# Power.net
KiCad netlist of a schematic drawn in Altium Designer
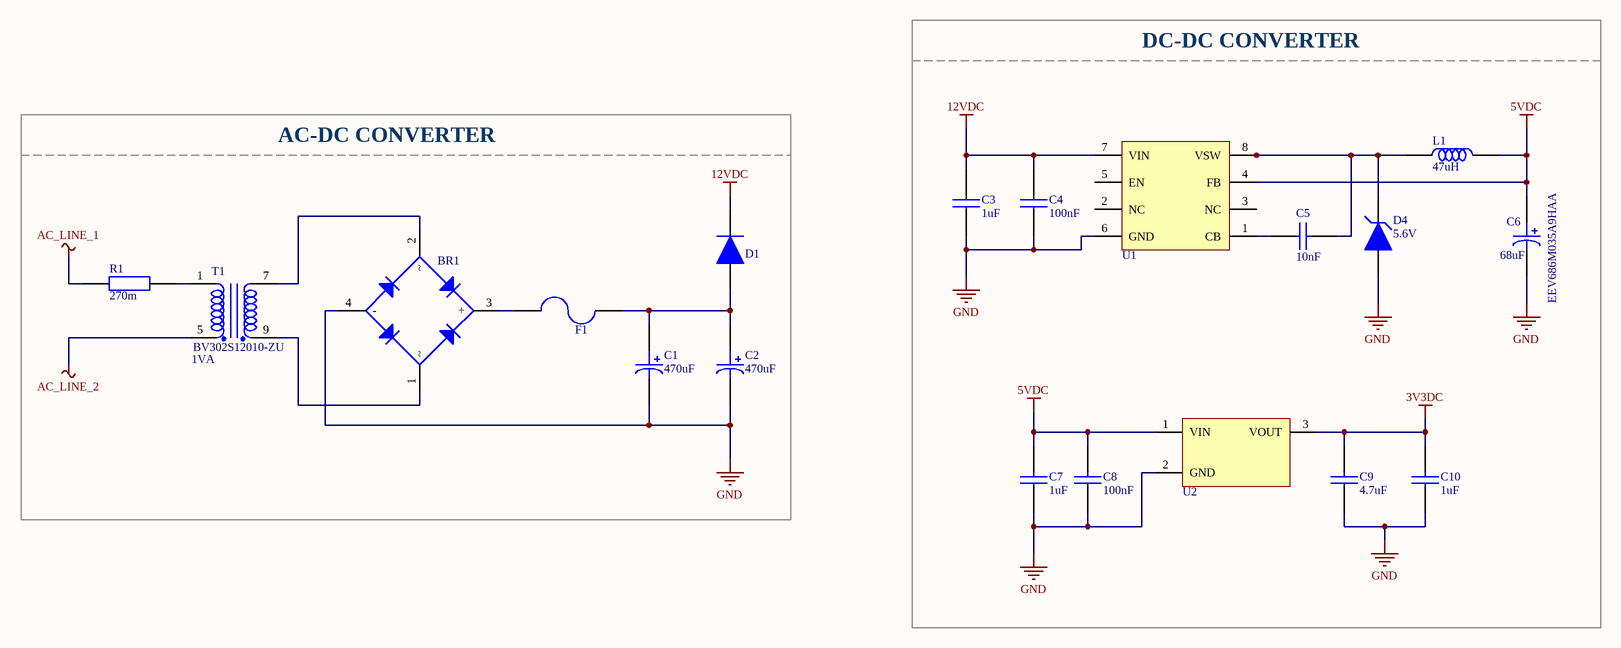
[diagram p0: Power.SchDoc]

(export (version "E")
  (design (tool "Eeschema 10.0.6"))
  (components
    (comp (ref "BR1")
      (value "DB105STR")
      (footprint "DB105STR")
      (description "Bridge Diode AC-DC")
      (fields (field (name "MANUFACTURER") "Sangdest Microelectronics") (field (name "DESIGNED BY") "BERK"))
      (libsource (lib "GuvenlikSistemi_Library") (part "DB105STR"))
    )
    (comp (ref "C1")
      (value "ESH477M050AH4AA")
      (footprint "CAP_RADIAL_D10_P5")
      (description "CAP ALU ELEC 470uF 50V RADIAL")
      (fields
        (field (name "MANUFACTURER") "KEMET")
        (field (name "TOLERANCE") "20%")
        (field (name "CAPACITANCE") "470uF")
        (field (name "DESIGNED BY") "BERK")
      )
      (libsource (lib "GuvenlikSistemi_Library") (part "CAP ALU ELEC 470uF 50V"))
    )
    (comp (ref "C2")
      (value "ESH477M050AH4AA")
      (footprint "CAP_RADIAL_D10_P5")
      (description "CAP ALU ELEC 470uF 50V RADIAL")
      (fields
        (field (name "MANUFACTURER") "KEMET")
        (field (name "TOLERANCE") "20%")
        (field (name "CAPACITANCE") "470uF")
        (field (name "DESIGNED BY") "BERK")
      )
      (libsource (lib "GuvenlikSistemi_Library") (part "CAP ALU ELEC 470uF 50V"))
    )
    (comp (ref "C3")
      (value "CL21B105KBFNNNE")
      (footprint "CAP_0805")
      (description "CAP CER 1uF %10 0805")
      (fields
        (field (name "MANUFACTURER") "Samsung")
        (field (name "TOLERANCE") "10%")
        (field (name "CAPACITANCE") "1uF")
        (field (name "DESIGNED BY") "BERK")
      )
      (libsource (lib "GuvenlikSistemi_Library") (part "CAP CER 1uF 0805"))
    )
    (comp (ref "C4")
      (value "CL21B104KBCNNNC")
      (footprint "CAP_0805")
      (description "CAP CER 100nF %10 0805")
      (fields
        (field (name "MANUFACTURER") "Samsung")
        (field (name "TOLERANCE") "10%")
        (field (name "CAPACITANCE") "100nF")
        (field (name "DESIGNED BY") "BERK")
      )
      (libsource (lib "GuvenlikSistemi_Library") (part "CAP CER 100nF 0805"))
    )
    (comp (ref "C5")
      (value "0603B103K160CT")
      (footprint "CAP_0603")
      (description "CAP CER 10nF %10 0603")
      (fields
        (field (name "MANUFACTURER") "Walsin Technologies")
        (field (name "TOLERANCE") "10%")
        (field (name "CAPACITANCE") "10nF")
        (field (name "DESIGNED BY") "BERK")
      )
      (libsource (lib "GuvenlikSistemi_Library") (part "CAP CER 10nF 0603"))
    )
    (comp (ref "C6")
      (value "EEV686M035A9HAA")
      (footprint "CAP_EEVseries")
      (description "Cap Aluminum Lytic 68uF 35V 20% (6.3 X 7.7mm) SMD 280mA 2000h 105C T/R")
      (fields
        (field (name "MANUFACTURER") "KEMET")
        (field (name "TOLERANCE") "20%")
        (field (name "CAPACITANCE") "68uF")
      )
      (libsource (lib "GuvenlikSistemi_Library") (part "CAP ALU 68uF"))
    )
    (comp (ref "C7")
      (value "CL21B105KBFNNNE")
      (footprint "CAP_0805")
      (description "CAP CER 1uF %10 0805")
      (fields
        (field (name "MANUFACTURER") "Samsung")
        (field (name "TOLERANCE") "10%")
        (field (name "CAPACITANCE") "1uF")
        (field (name "DESIGNED BY") "BERK")
      )
      (libsource (lib "GuvenlikSistemi_Library") (part "CAP CER 1uF 0805"))
    )
    (comp (ref "C8")
      (value "CL21B104KBCNNNC")
      (footprint "CAP_0805")
      (description "CAP CER 100nF %10 0805")
      (fields
        (field (name "MANUFACTURER") "Samsung")
        (field (name "TOLERANCE") "10%")
        (field (name "CAPACITANCE") "100nF")
        (field (name "DESIGNED BY") "BERK")
      )
      (libsource (lib "GuvenlikSistemi_Library") (part "CAP CER 100nF 0805"))
    )
    (comp (ref "C9")
      (value "CL21A475KAQNNNE")
      (footprint "CAP_0805")
      (description "CAP CER 4.7uF %10 0805")
      (fields
        (field (name "MANUFACTURER") "Samsung")
        (field (name "TOLERANCE") "10%")
        (field (name "CAPACITANCE") "4.7uF")
        (field (name "DESIGNED BY") "BERK")
      )
      (libsource (lib "GuvenlikSistemi_Library") (part "CAP CER 4.7uF 0805"))
    )
    (comp (ref "C10")
      (value "CL21B105KBFNNNE")
      (footprint "CAP_0805")
      (description "CAP CER 1uF %10 0805")
      (fields
        (field (name "MANUFACTURER") "Samsung")
        (field (name "TOLERANCE") "10%")
        (field (name "CAPACITANCE") "1uF")
        (field (name "DESIGNED BY") "BERK")
      )
      (libsource (lib "GuvenlikSistemi_Library") (part "CAP CER 1uF 0805"))
    )
    (comp (ref "D1")
      (value "1N4148WS")
      (footprint "SOD323F")
      (description "Diode, Single, 75 V, 150 mA, 1 V, 4 ns")
      (fields
        (field (name "MANUFACTURER") "ON Semiconductor / Fairchild")
        (field (name "DESIGNED BY") "BERK")
      )
      (libsource (lib "GuvenlikSistemi_Library") (part "1N4148WS"))
    )
    (comp (ref "D4")
      (value "1SMB5919BT3G")
      (footprint "SMB")
      (description "Diode Zener Single 5.6V 5% 3W 2-Pin SMB T/R")
      (fields
        (field (name "MANUFACTURER") "ON Semiconductor")
        (field (name "TOLERANCE") "5%")
        (field (name "WORKING VOLTAGE") "5.6V")
        (field (name "DESIGNED BY") "BERK")
      )
      (libsource (lib "GuvenlikSistemi_Library") (part "1SMB5919BT3G"))
    )
    (comp (ref "F1")
      (value "3413.0216.22")
      (footprint "3413.0216.22")
      (description "FUSE BRD MNT 1A 32VAC 63VDC 1206")
      (fields (field (name "MANUFACTURER") "Schurter") (field (name "DESIGNED BY") "BERK"))
      (libsource (lib "GuvenlikSistemi_Library") (part "FUSE 3413.0216.22"))
    )
    (comp (ref "L1")
      (value "78438335470")
      (footprint "IND_1212")
      (description "FIXED IND 47UH 390MA 2.3 OHM SMD")
      (fields
        (field (name "MANUFACTURER") "Wurth Electronics")
        (field (name "TOLERANCE") "30%")
        (field (name "INDUCTANCE") "47uH")
        (field (name "DESIGNED BY") "BERK")
      )
      (libsource (lib "GuvenlikSistemi_Library") (part "IND 47uH"))
    )
    (comp (ref "R1")
      (value "5WD27")
      (footprint "RES_AXIAL_W")
      (description "Resistor 5 Watt Cermet Wirewound Flameproof .27 Ohm 5% Axial Lead")
      (fields
        (field (name "MANUFACTURER") "NTE Electronics")
        (field (name "TOLERANCE") "5%")
        (field (name "RESISTANCE") "270m")
        (field (name "DESIGNED BY") "BERK")
      )
      (libsource (lib "GuvenlikSistemi_Library") (part "5WD27"))
    )
    (comp (ref "T1")
      (value "BV302S12010-ZU")
      (footprint "BV302S")
      (description "230-12 Transformer 1VA")
      (fields
        (field (name "MANUFACTURER") "Zettler Magnetics")
        (field (name "RATED POWER") "1VA")
        (field (name "DESIGNED BY") "BERK")
      )
      (libsource (lib "GuvenlikSistemi_Library") (part "BV302S12010-ZU"))
    )
    (comp (ref "U1")
      (value "LM2675MX-12/NOPB")
      (footprint "SOIC8")
      (description "Switching Voltage Regulators Pwr Cnvtr Hi Eff 1A SD Vtg Reg")
      (fields (field (name "MANUFACTURER") "TI National Semiconductor") (field (name "DESIGNED BY") "BERK"))
      (libsource (lib "GuvenlikSistemi_Library") (part "LM2675MX-12/NOPB"))
    )
    (comp (ref "U2")
      (value "AP7361-33E-13")
      (footprint "SOT223")
      (description "LDO Regulator Pos 3.3V 1A 4-Pin(3+Tab) SOT-223 T/R")
      (fields (field (name "MANUFACTURER") "Diodes") (field (name "DESIGNED BY") "BERK"))
      (libsource (lib "GuvenlikSistemi_Library") (part "AP7361-33E-13"))
    )
  )
  (nets
    (net (code "1") (name "3V3DC") (class "Default")
      (node (ref "C10") (pin "2") (pinfunction "2_2") (pintype "passive"))
      (node (ref "C9") (pin "2") (pinfunction "2_2") (pintype "passive"))
      (node (ref "U2") (pin "3") (pinfunction "VOUT_3") (pintype "passive"))
    )
    (net (code "2") (name "5VDC") (class "Default")
      (node (ref "C6") (pin "1") (pinfunction "1_1") (pintype "passive"))
      (node (ref "C7") (pin "2") (pinfunction "2_2") (pintype "passive"))
      (node (ref "C8") (pin "2") (pinfunction "2_2") (pintype "passive"))
      (node (ref "L1") (pin "2") (pinfunction "2_2") (pintype "passive"))
      (node (ref "U1") (pin "4") (pinfunction "FB_4") (pintype "passive"))
      (node (ref "U2") (pin "1") (pinfunction "VIN_1") (pintype "passive"))
    )
    (net (code "3") (name "12VDC") (class "Default")
      (node (ref "C3") (pin "2") (pinfunction "2_2") (pintype "passive"))
      (node (ref "C4") (pin "2") (pinfunction "2_2") (pintype "passive"))
      (node (ref "D1") (pin "1") (pinfunction "1_1") (pintype "power_in"))
      (node (ref "U1") (pin "7") (pinfunction "VIN_7") (pintype "passive"))
    )
    (net (code "4") (name "AC_LINE_1") (class "Default")
      (node (ref "R1") (pin "1") (pinfunction "1_1") (pintype "passive"))
    )
    (net (code "5") (name "AC_LINE_2") (class "Default")
      (node (ref "T1") (pin "5") (pinfunction "5_5") (pintype "passive"))
    )
    (net (code "6") (name "GND") (class "Default")
      (node (ref "BR1") (pin "4") (pinfunction "-_4") (pintype "passive"))
      (node (ref "C1") (pin "2") (pinfunction "2_2") (pintype "passive"))
      (node (ref "C10") (pin "1") (pinfunction "1_1") (pintype "passive"))
      (node (ref "C2") (pin "2") (pinfunction "2_2") (pintype "passive"))
      (node (ref "C3") (pin "1") (pinfunction "1_1") (pintype "passive"))
      (node (ref "C4") (pin "1") (pinfunction "1_1") (pintype "passive"))
      (node (ref "C6") (pin "2") (pinfunction "2_2") (pintype "passive"))
      (node (ref "C7") (pin "1") (pinfunction "1_1") (pintype "passive"))
      (node (ref "C8") (pin "1") (pinfunction "1_1") (pintype "passive"))
      (node (ref "C9") (pin "1") (pinfunction "1_1") (pintype "passive"))
      (node (ref "D4") (pin "A") (pinfunction "A_A") (pintype "passive"))
      (node (ref "U1") (pin "6") (pinfunction "GND_6") (pintype "passive"))
      (node (ref "U2") (pin "2") (pinfunction "GND_2") (pintype "passive"))
    )
    (net (code "7") (name "Net-(BR1-+)") (class "Default")
      (node (ref "BR1") (pin "3") (pinfunction "+_3") (pintype "passive"))
      (node (ref "F1") (pin "1") (pinfunction "1_1") (pintype "passive"))
    )
    (net (code "8") (name "Net-(BR1-~-Pad1)") (class "Default")
      (node (ref "BR1") (pin "1") (pinfunction "~_1") (pintype "passive"))
      (node (ref "T1") (pin "9") (pinfunction "9_9") (pintype "passive"))
    )
    (net (code "9") (name "Net-(BR1-~-Pad2)") (class "Default")
      (node (ref "BR1") (pin "2") (pinfunction "~_2") (pintype "passive"))
      (node (ref "T1") (pin "7") (pinfunction "7_7") (pintype "passive"))
    )
    (net (code "10") (name "Net-(C1-Pad1)") (class "Default")
      (node (ref "C1") (pin "1") (pinfunction "1_1") (pintype "passive"))
      (node (ref "C2") (pin "1") (pinfunction "1_1") (pintype "passive"))
      (node (ref "D1") (pin "2") (pinfunction "2_2") (pintype "power_in"))
      (node (ref "F1") (pin "2") (pinfunction "2_2") (pintype "passive"))
    )
    (net (code "11") (name "Net-(R1-Pad2)") (class "Default")
      (node (ref "R1") (pin "2") (pinfunction "2_2") (pintype "passive"))
      (node (ref "T1") (pin "1") (pinfunction "1_1") (pintype "passive"))
    )
    (net (code "12") (name "Net-(U1-CB)") (class "Default")
      (node (ref "C5") (pin "1") (pinfunction "1_1") (pintype "passive"))
      (node (ref "U1") (pin "1") (pinfunction "CB_1") (pintype "passive"))
    )
    (net (code "13") (name "Net-(U1-VSW)") (class "Default")
      (node (ref "C5") (pin "2") (pinfunction "2_2") (pintype "passive"))
      (node (ref "D4") (pin "C") (pinfunction "C_C") (pintype "passive"))
      (node (ref "L1") (pin "1") (pinfunction "1_1") (pintype "passive"))
      (node (ref "U1") (pin "8") (pinfunction "VSW_8") (pintype "passive"))
    )
    (net (code "14") (name "unconnected-(U1-EN-Pad5)") (class "Default")
      (node (ref "U1") (pin "5") (pinfunction "EN_5") (pintype "passive"))
    )
    (net (code "15") (name "unconnected-(U1-NC-Pad2)") (class "Default")
      (node (ref "U1") (pin "2") (pinfunction "NC_2") (pintype "passive"))
    )
    (net (code "16") (name "unconnected-(U1-NC-Pad3)") (class "Default")
      (node (ref "U1") (pin "3") (pinfunction "NC_3") (pintype "passive"))
    )
  )
)
